# PowerBoard.net
KiCad netlist of a schematic drawn in EAGLE
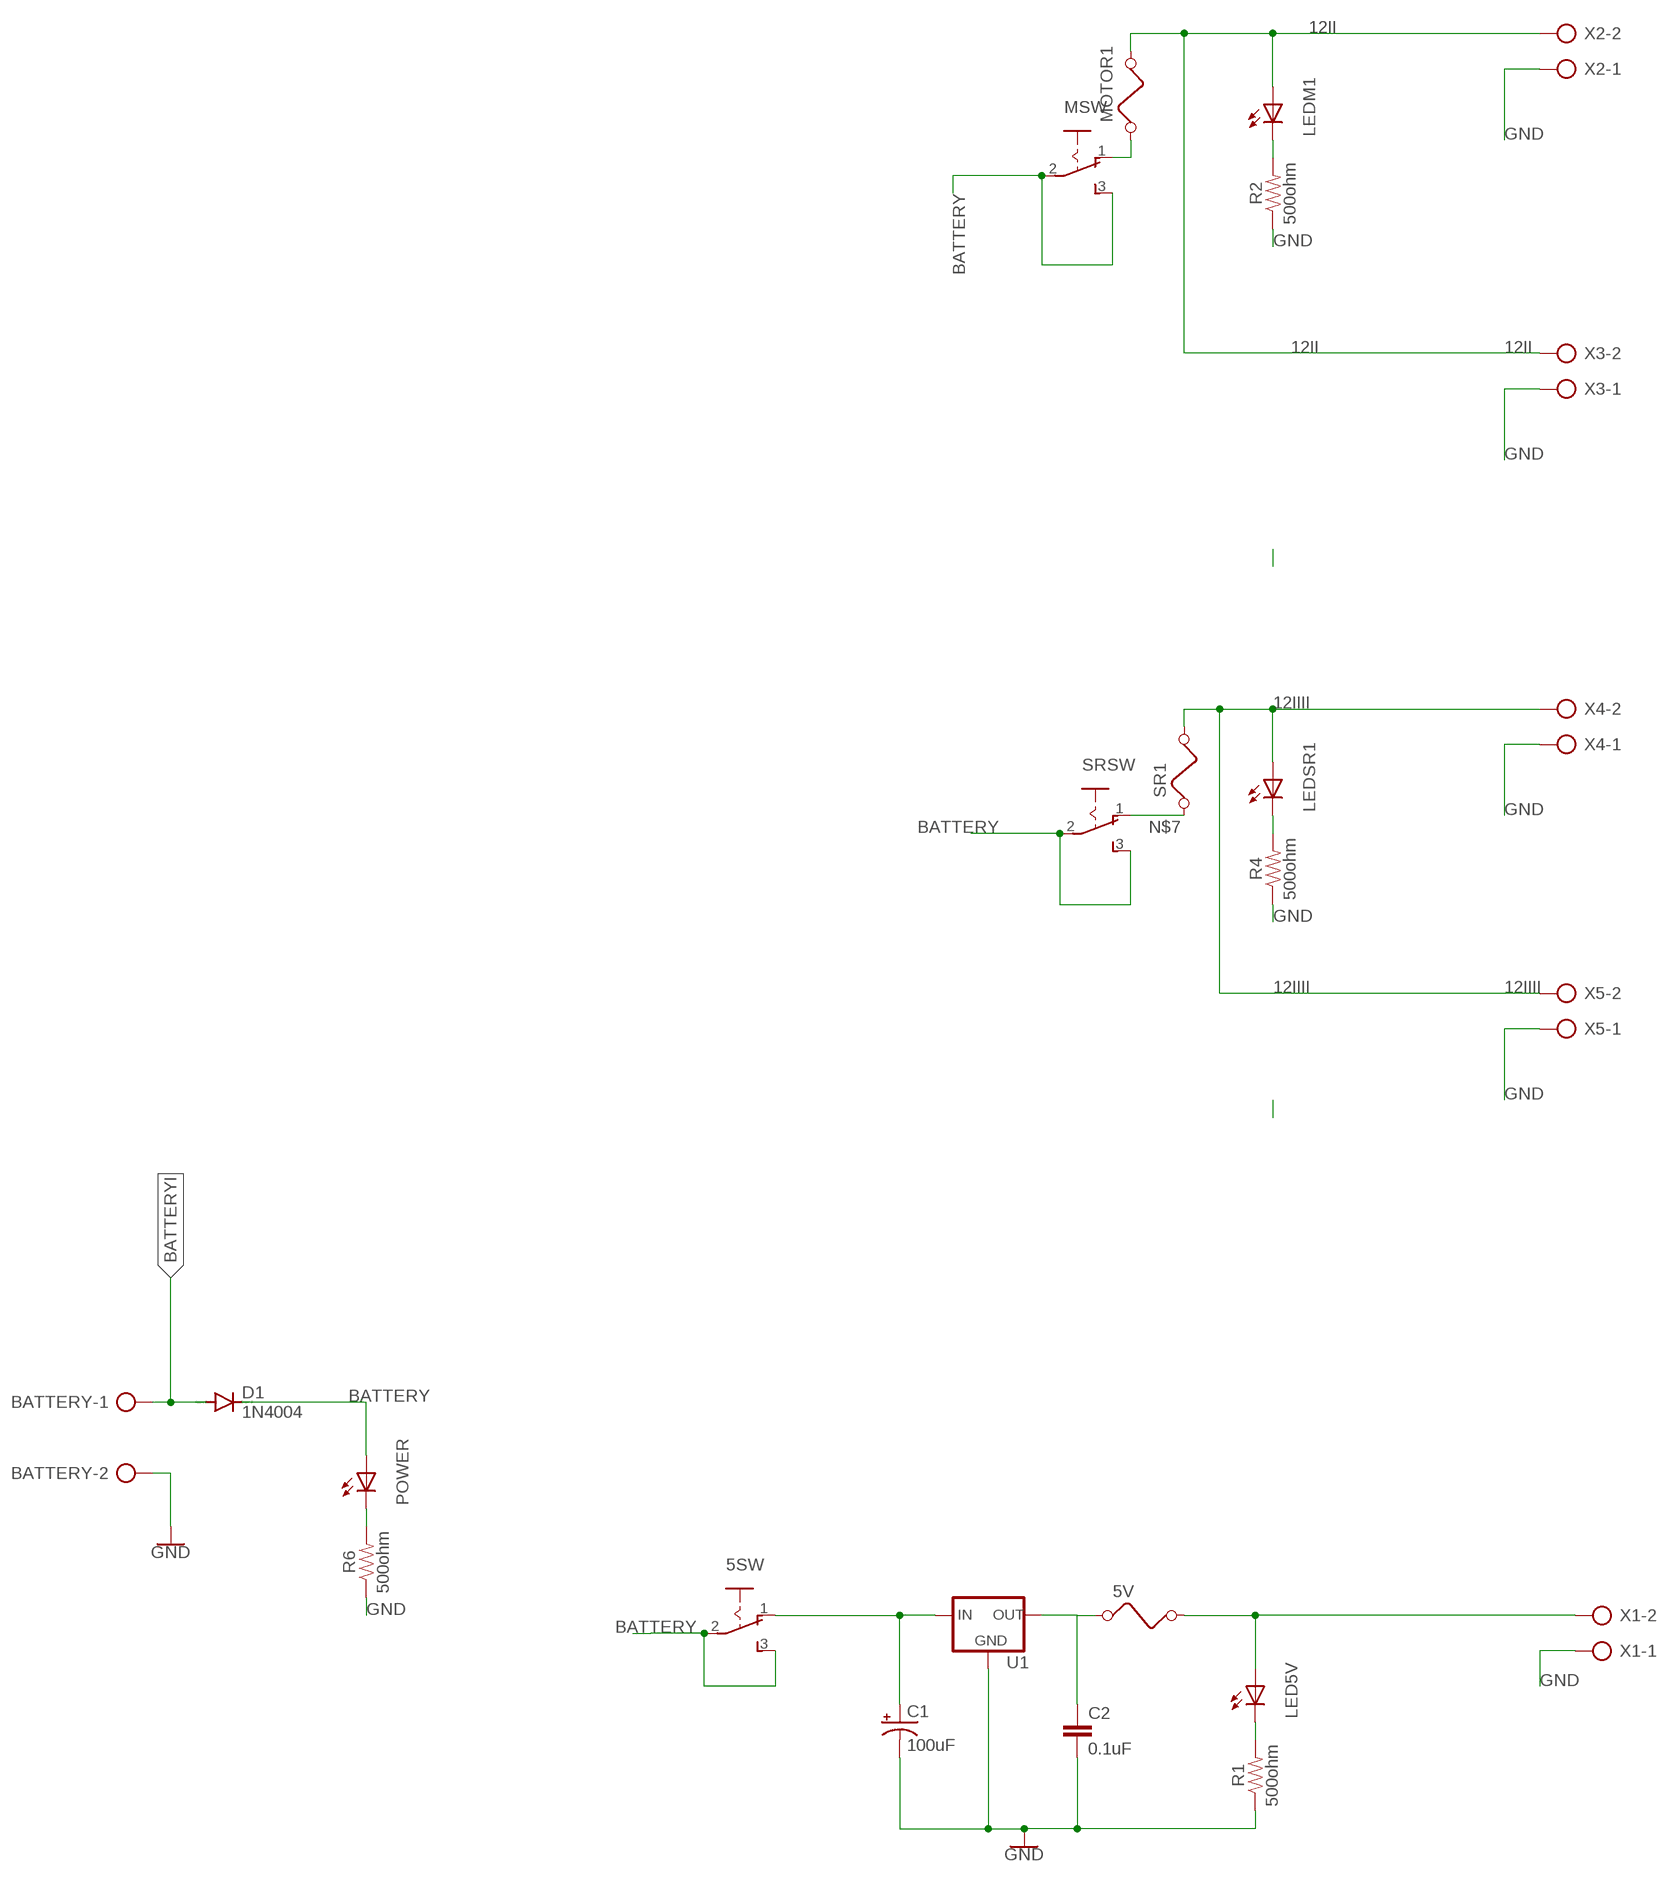
[diagram p0: schematic, sheet 1]

(export (version "E")
  (design (tool "Eeschema 10.0.6"))
  (components
    (comp (ref "5SW")
      (value "255SB")
      (footprint "eagle-import:255SB")
      (libsource (lib "eagle-import") (part "255SB"))
    )
    (comp (ref "5V")
      (value "FUSE")
      (footprint "eagle-import:FUSE")
      (libsource (lib "eagle-import") (part "FUSE"))
    )
    (comp (ref "BATTERY")
      (value "AK500/2-H")
      (footprint "eagle-import:AK500_2-H")
      (libsource (lib "eagle-import") (part "AK500/2-H"))
    )
    (comp (ref "C1")
      (value "100uF")
      (footprint "eagle-import:CPOL-RADIAL-2.5MM-6.5MM")
      (libsource (lib "eagle-import") (part "100UF-POLAR-RADIAL-2.5MM-25V-20%"))
    )
    (comp (ref "C2")
      (value "0.1uF")
      (footprint "eagle-import:CAP-PTH-SMALL-KIT")
      (libsource (lib "eagle-import") (part "0.1UF-KIT-EZ-50V-20%"))
    )
    (comp (ref "D1")
      (value "1N4004")
      (footprint "eagle-import:DO41-10")
      (libsource (lib "eagle-import") (part "1N4004"))
    )
    (comp (ref "LED5V")
      (value "LED3MM")
      (footprint "eagle-import:LED3MM")
      (libsource (lib "eagle-import") (part "LED3MM"))
    )
    (comp (ref "LEDM1")
      (value "LED3MM")
      (footprint "eagle-import:LED3MM")
      (libsource (lib "eagle-import") (part "LED3MM"))
    )
    (comp (ref "LEDSR1")
      (value "LED3MM")
      (footprint "eagle-import:LED3MM")
      (libsource (lib "eagle-import") (part "LED3MM"))
    )
    (comp (ref "MOTOR1")
      (value "FUSE")
      (footprint "eagle-import:FUSE")
      (libsource (lib "eagle-import") (part "FUSE"))
    )
    (comp (ref "MSW")
      (value "255SB")
      (footprint "eagle-import:255SB")
      (libsource (lib "eagle-import") (part "255SB"))
    )
    (comp (ref "POWER")
      (value "LED3MM")
      (footprint "eagle-import:LED3MM")
      (libsource (lib "eagle-import") (part "LED3MM"))
    )
    (comp (ref "R1")
      (value "500ohm")
      (footprint "eagle-import:AXIAL-0.3")
      (libsource (lib "eagle-import") (part "10MOHM-HORIZ-1/4W-5%"))
    )
    (comp (ref "R2")
      (value "500ohm")
      (footprint "eagle-import:AXIAL-0.3")
      (libsource (lib "eagle-import") (part "10MOHM-HORIZ-1/4W-5%"))
    )
    (comp (ref "R4")
      (value "500ohm")
      (footprint "eagle-import:AXIAL-0.3")
      (libsource (lib "eagle-import") (part "10MOHM-HORIZ-1/4W-5%"))
    )
    (comp (ref "R6")
      (value "500ohm")
      (footprint "eagle-import:AXIAL-0.3")
      (libsource (lib "eagle-import") (part "10MOHM-HORIZ-1/4W-5%"))
    )
    (comp (ref "SR1")
      (value "FUSE")
      (footprint "eagle-import:FUSE")
      (libsource (lib "eagle-import") (part "FUSE"))
    )
    (comp (ref "SRSW")
      (value "255SB")
      (footprint "eagle-import:255SB")
      (libsource (lib "eagle-import") (part "255SB"))
    )
    (comp (ref "U1")
      (value "78XXS")
      (footprint "eagle-import:78XXS")
      (libsource (lib "eagle-import") (part "78XXS"))
    )
    (comp (ref "X1")
      (value "AK500/2-H")
      (footprint "eagle-import:AK500_2-H")
      (libsource (lib "eagle-import") (part "AK500/2-H"))
    )
    (comp (ref "X2")
      (value "AK500/2-H")
      (footprint "eagle-import:AK500_2-H")
      (libsource (lib "eagle-import") (part "AK500/2-H"))
    )
    (comp (ref "X3")
      (value "AK500/2-H")
      (footprint "eagle-import:AK500_2-H")
      (libsource (lib "eagle-import") (part "AK500/2-H"))
    )
    (comp (ref "X4")
      (value "AK500/2-H")
      (footprint "eagle-import:AK500_2-H")
      (libsource (lib "eagle-import") (part "AK500/2-H"))
    )
    (comp (ref "X5")
      (value "AK500/2-H")
      (footprint "eagle-import:AK500_2-H")
      (libsource (lib "eagle-import") (part "AK500/2-H"))
    )
  )
  (nets
    (net (code "1") (name "/12II") (class "Default")
      (node (ref "LEDM1") (pin "A") (pinfunction "A_A") (pintype "passive"))
      (node (ref "MOTOR1") (pin "2") (pinfunction "2_2") (pintype "passive"))
      (node (ref "X2") (pin "2") (pinfunction "KL_2") (pintype "passive"))
      (node (ref "X3") (pin "2") (pinfunction "KL_2") (pintype "passive"))
    )
    (net (code "2") (name "/12IIII") (class "Default")
      (node (ref "LEDSR1") (pin "A") (pinfunction "A_A") (pintype "passive"))
      (node (ref "SR1") (pin "2") (pinfunction "2_2") (pintype "passive"))
      (node (ref "X4") (pin "2") (pinfunction "KL_2") (pintype "passive"))
      (node (ref "X5") (pin "2") (pinfunction "KL_2") (pintype "passive"))
    )
    (net (code "3") (name "/BATTERY") (class "Default")
      (node (ref "5SW") (pin "2") (pinfunction "P_2") (pintype "passive"))
      (node (ref "5SW") (pin "3") (pinfunction "S_3") (pintype "passive"))
      (node (ref "D1") (pin "C") (pinfunction "C_C") (pintype "passive"))
      (node (ref "MSW") (pin "2") (pinfunction "P_2") (pintype "passive"))
      (node (ref "MSW") (pin "3") (pinfunction "S_3") (pintype "passive"))
      (node (ref "POWER") (pin "A") (pinfunction "A_A") (pintype "passive"))
      (node (ref "SRSW") (pin "2") (pinfunction "P_2") (pintype "passive"))
      (node (ref "SRSW") (pin "3") (pinfunction "S_3") (pintype "passive"))
    )
    (net (code "4") (name "/N$7") (class "Default")
      (node (ref "SR1") (pin "1") (pinfunction "1_1") (pintype "passive"))
      (node (ref "SRSW") (pin "1") (pinfunction "O_1") (pintype "passive"))
    )
    (net (code "5") (name "BATTERYI") (class "Default")
      (node (ref "BATTERY") (pin "1") (pinfunction "KL_1") (pintype "passive"))
      (node (ref "D1") (pin "A") (pinfunction "A_A") (pintype "passive"))
    )
    (net (code "6") (name "GND") (class "Default")
      (node (ref "BATTERY") (pin "2") (pinfunction "KL_2") (pintype "passive"))
      (node (ref "C1") (pin "2") (pinfunction "-_2") (pintype "passive"))
      (node (ref "C2") (pin "2") (pinfunction "2_2") (pintype "passive"))
      (node (ref "R1") (pin "P$1") (pinfunction "1_P$1") (pintype "passive"))
      (node (ref "R2") (pin "P$1") (pinfunction "1_P$1") (pintype "passive"))
      (node (ref "R4") (pin "P$1") (pinfunction "1_P$1") (pintype "passive"))
      (node (ref "R6") (pin "P$1") (pinfunction "1_P$1") (pintype "passive"))
      (node (ref "U1") (pin "GND") (pinfunction "GND_GND") (pintype "input"))
      (node (ref "X1") (pin "1") (pinfunction "KL_1") (pintype "passive"))
      (node (ref "X2") (pin "1") (pinfunction "KL_1") (pintype "passive"))
      (node (ref "X3") (pin "1") (pinfunction "KL_1") (pintype "passive"))
      (node (ref "X4") (pin "1") (pinfunction "KL_1") (pintype "passive"))
      (node (ref "X5") (pin "1") (pinfunction "KL_1") (pintype "passive"))
    )
    (net (code "7") (name "Net-(5SW-O)") (class "Default")
      (node (ref "5SW") (pin "1") (pinfunction "O_1") (pintype "passive"))
      (node (ref "C1") (pin "1") (pinfunction "+_1") (pintype "passive"))
      (node (ref "U1") (pin "IN") (pinfunction "IN_IN") (pintype "input"))
    )
    (net (code "8") (name "Net-(5V-Pad1)") (class "Default")
      (node (ref "5V") (pin "1") (pinfunction "1_1") (pintype "passive"))
      (node (ref "C2") (pin "1") (pinfunction "1_1") (pintype "passive"))
      (node (ref "U1") (pin "OUT") (pinfunction "OUT_OUT") (pintype "passive"))
    )
    (net (code "9") (name "Net-(LED5V-C)") (class "Default")
      (node (ref "LED5V") (pin "K") (pinfunction "C_K") (pintype "passive"))
      (node (ref "R1") (pin "P$2") (pinfunction "2_P$2") (pintype "passive"))
    )
    (net (code "10") (name "Net-(LEDM1-C)") (class "Default")
      (node (ref "LEDM1") (pin "K") (pinfunction "C_K") (pintype "passive"))
      (node (ref "R2") (pin "P$2") (pinfunction "2_P$2") (pintype "passive"))
    )
    (net (code "11") (name "Net-(LEDSR1-C)") (class "Default")
      (node (ref "LEDSR1") (pin "K") (pinfunction "C_K") (pintype "passive"))
      (node (ref "R4") (pin "P$2") (pinfunction "2_P$2") (pintype "passive"))
    )
    (net (code "12") (name "Net-(MSW-O)") (class "Default")
      (node (ref "MOTOR1") (pin "1") (pinfunction "1_1") (pintype "passive"))
      (node (ref "MSW") (pin "1") (pinfunction "O_1") (pintype "passive"))
    )
    (net (code "13") (name "Net-(POWER-C)") (class "Default")
      (node (ref "POWER") (pin "K") (pinfunction "C_K") (pintype "passive"))
      (node (ref "R6") (pin "P$2") (pinfunction "2_P$2") (pintype "passive"))
    )
    (net (code "14") (name "Net-(X1B-KL)") (class "Default")
      (node (ref "5V") (pin "2") (pinfunction "2_2") (pintype "passive"))
      (node (ref "LED5V") (pin "A") (pinfunction "A_A") (pintype "passive"))
      (node (ref "X1") (pin "2") (pinfunction "KL_2") (pintype "passive"))
    )
  )
)
